# Homebrew_Companion_Board_v2.net
KiCad netlist of a schematic drawn in EAGLE
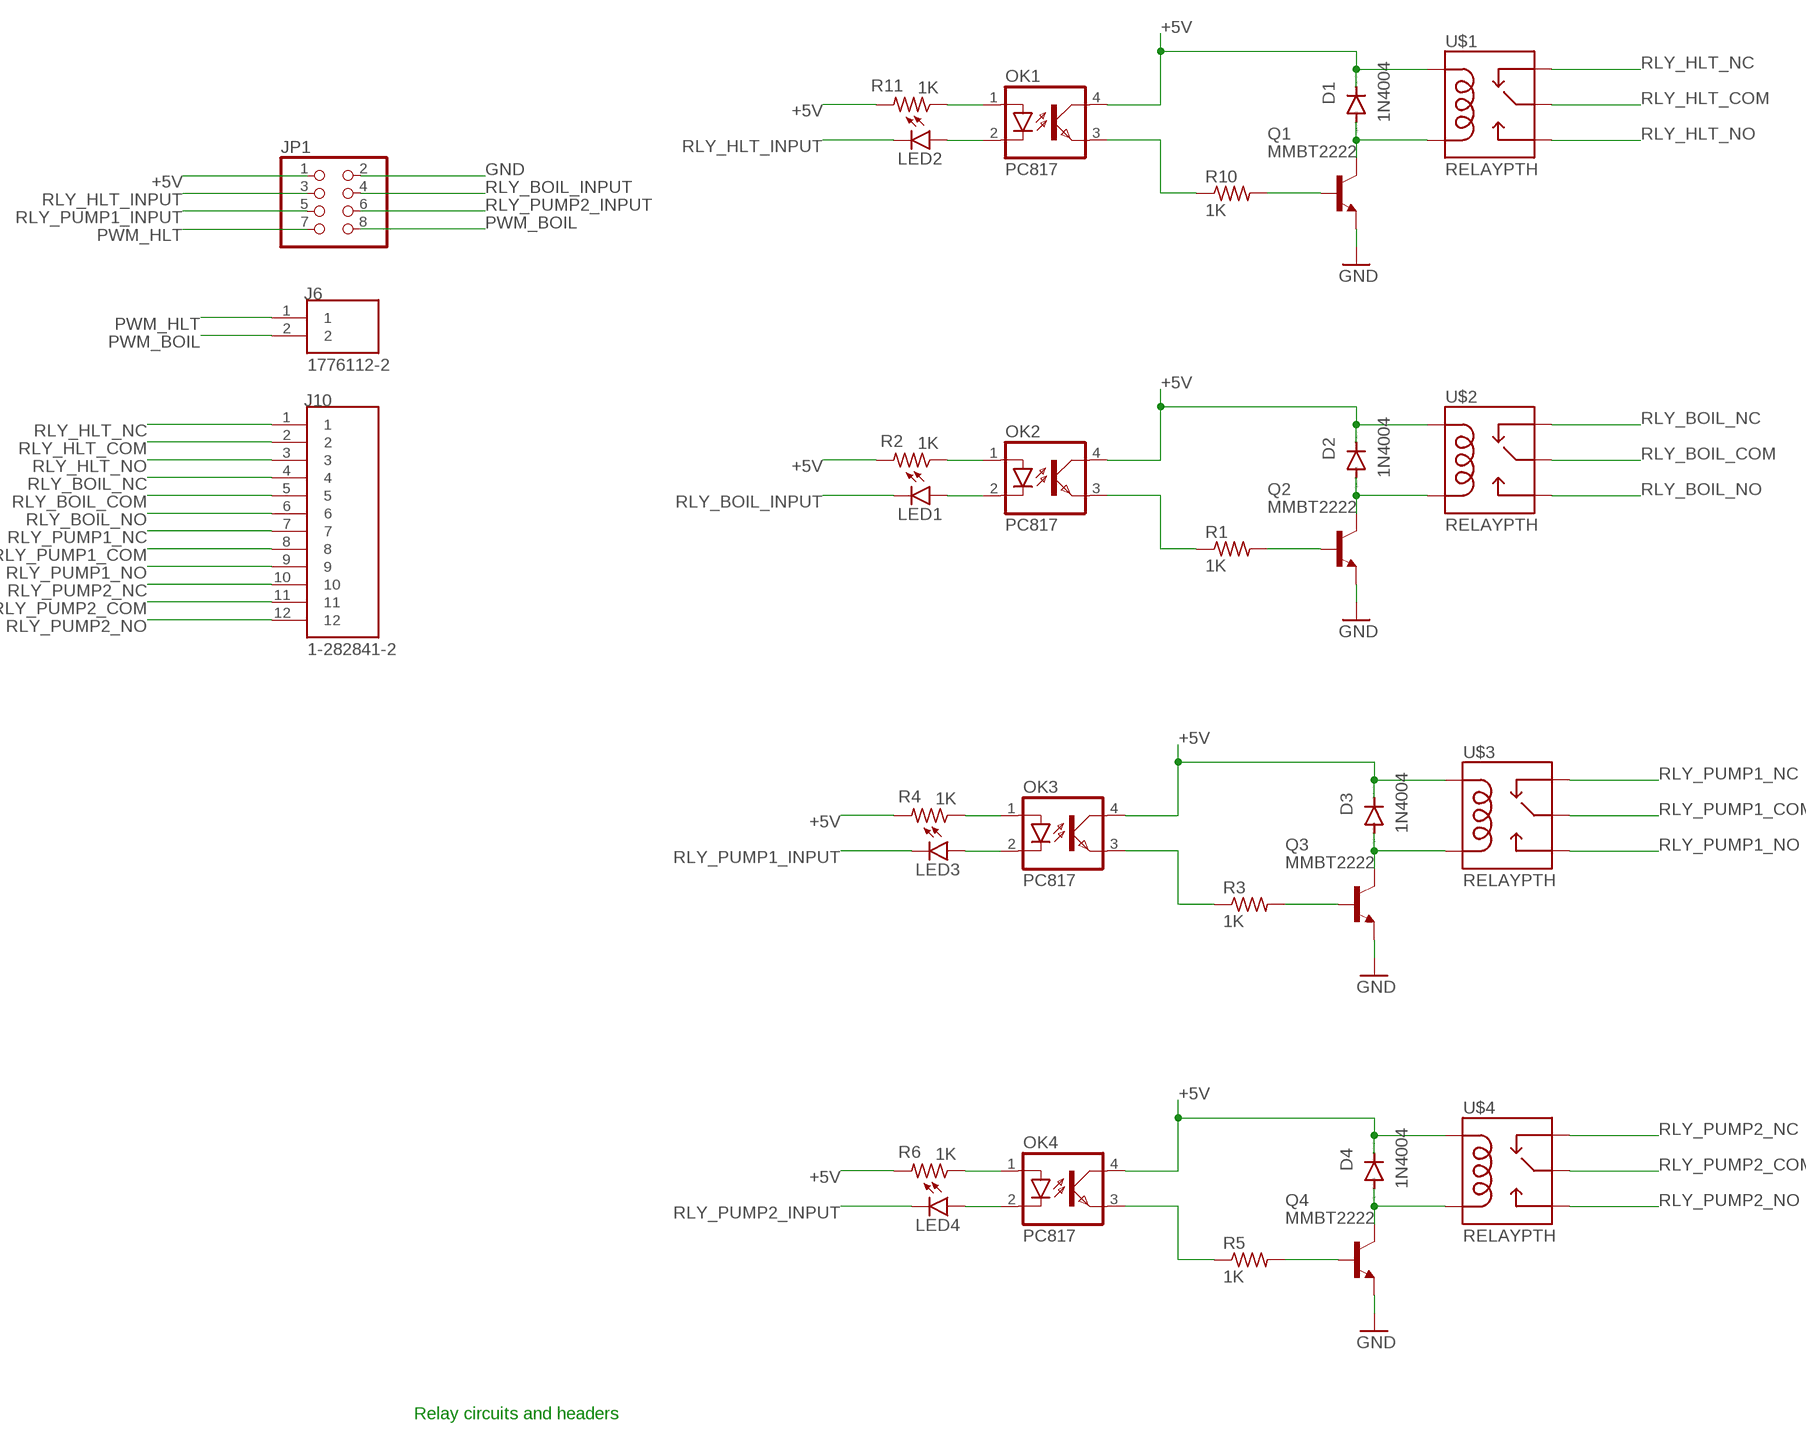
[diagram p0: schematic, sheet 1]

(export (version "E")
  (design (tool "Eeschema 10.0.6"))
  (components
    (comp (ref "D1")
      (value "1N4004")
      (footprint "eagle-import:DO41-10")
      (fields (field (name "MF") "DIODES INC.") (field (name "MPN") "1N4007-T"))
      (libsource (lib "eagle-import") (part "1N4004"))
    )
    (comp (ref "D2")
      (value "1N4004")
      (footprint "eagle-import:DO41-10")
      (fields (field (name "MF") "DIODES INC.") (field (name "MPN") "1N4007-T"))
      (libsource (lib "eagle-import") (part "1N4004"))
    )
    (comp (ref "D3")
      (value "1N4004")
      (footprint "eagle-import:DO41-10")
      (fields (field (name "MF") "DIODES INC.") (field (name "MPN") "1N4007-T"))
      (libsource (lib "eagle-import") (part "1N4004"))
    )
    (comp (ref "D4")
      (value "1N4004")
      (footprint "eagle-import:DO41-10")
      (fields (field (name "MF") "DIODES INC.") (field (name "MPN") "1N4007-T"))
      (libsource (lib "eagle-import") (part "1N4004"))
    )
    (comp (ref "J6")
      (value "1776112-2")
      (footprint "eagle-import:TE_1776112-2")
      (fields (field (name "MF") "TE Connectivity") (field (name "MF_1") "AMP - TE CONNECTIVITY"))
      (libsource (lib "eagle-import") (part "1776112-2"))
    )
    (comp (ref "J10")
      (value "1-282841-2")
      (footprint "eagle-import:TE_1-282841-2")
      (fields (field (name "MF") "TE Connectivity") (field (name "MF_1") "AMP - TE CONNECTIVITY"))
      (libsource (lib "eagle-import") (part "1-282841-2"))
    )
    (comp (ref "JP1")
      (value "PINHD-2X4")
      (footprint "eagle-import:2X04")
      (fields (field (name "MF") "AMP - TE CONNECTIVITY") (field (name "MPN") "826634-4"))
      (libsource (lib "eagle-import") (part "PINHD-2X4"))
    )
    (comp (ref "LED1")
      (value "LEDCHIP-LED0805")
      (footprint "eagle-import:CHIP-LED0805")
      (fields (field (name "MF") "DIALIGHT") (field (name "MPN") "5988110107F"))
      (libsource (lib "eagle-import") (part "LEDCHIP-LED0805"))
    )
    (comp (ref "LED2")
      (value "LEDCHIP-LED0805")
      (footprint "eagle-import:CHIP-LED0805")
      (fields (field (name "MF") "DIALIGHT") (field (name "MPN") "5988110107F"))
      (libsource (lib "eagle-import") (part "LEDCHIP-LED0805"))
    )
    (comp (ref "LED3")
      (value "LEDCHIP-LED0805")
      (footprint "eagle-import:CHIP-LED0805")
      (fields (field (name "MF") "DIALIGHT") (field (name "MPN") "5988110107F"))
      (libsource (lib "eagle-import") (part "LEDCHIP-LED0805"))
    )
    (comp (ref "LED4")
      (value "LEDCHIP-LED0805")
      (footprint "eagle-import:CHIP-LED0805")
      (fields (field (name "MF") "DIALIGHT") (field (name "MPN") "5988110107F"))
      (libsource (lib "eagle-import") (part "LEDCHIP-LED0805"))
    )
    (comp (ref "OK1")
      (value "PC817")
      (footprint "eagle-import:DIL04")
      (fields
        (field (name "MPN") "PC817X4J000F")
        (field (name "MF") "BROADCOM")
        (field (name "MPN_1") "HCPL-817-000E")
        (field (name "OC_NEWARK") "36J9610")
      )
      (libsource (lib "eagle-import") (part "PC817"))
    )
    (comp (ref "OK2")
      (value "PC817")
      (footprint "eagle-import:DIL04")
      (fields
        (field (name "MPN") "PC817X4J000F")
        (field (name "MF") "BROADCOM")
        (field (name "MPN_1") "HCPL-817-000E")
        (field (name "OC_NEWARK") "36J9610")
      )
      (libsource (lib "eagle-import") (part "PC817"))
    )
    (comp (ref "OK3")
      (value "PC817")
      (footprint "eagle-import:DIL04")
      (fields
        (field (name "MPN") "PC817X4J000F")
        (field (name "MF") "BROADCOM")
        (field (name "MPN_1") "HCPL-817-000E")
        (field (name "OC_NEWARK") "36J9610")
      )
      (libsource (lib "eagle-import") (part "PC817"))
    )
    (comp (ref "OK4")
      (value "PC817")
      (footprint "eagle-import:DIL04")
      (fields
        (field (name "MPN") "PC817X4J000F")
        (field (name "MF") "BROADCOM")
        (field (name "MPN_1") "HCPL-817-000E")
        (field (name "OC_NEWARK") "36J9610")
      )
      (libsource (lib "eagle-import") (part "PC817"))
    )
    (comp (ref "Q1")
      (value "MMBT2222")
      (footprint "eagle-import:SOT23-BEC")
      (fields
        (field (name "MF") "ON Semiconductor")
        (field (name "MF_1") "DIODES INC.")
        (field (name "MPN") "MMBT2222A-7-F")
      )
      (libsource (lib "eagle-import") (part "MMBT2222"))
    )
    (comp (ref "Q2")
      (value "MMBT2222")
      (footprint "eagle-import:SOT23-BEC")
      (fields
        (field (name "MF") "ON Semiconductor")
        (field (name "MF_1") "DIODES INC.")
        (field (name "MPN") "MMBT2222A-7-F")
      )
      (libsource (lib "eagle-import") (part "MMBT2222"))
    )
    (comp (ref "Q3")
      (value "MMBT2222")
      (footprint "eagle-import:SOT23-BEC")
      (fields
        (field (name "MF") "ON Semiconductor")
        (field (name "MF_1") "DIODES INC.")
        (field (name "MPN") "MMBT2222A-7-F")
      )
      (libsource (lib "eagle-import") (part "MMBT2222"))
    )
    (comp (ref "Q4")
      (value "MMBT2222")
      (footprint "eagle-import:SOT23-BEC")
      (fields
        (field (name "MF") "ON Semiconductor")
        (field (name "MF_1") "DIODES INC.")
        (field (name "MPN") "MMBT2222A-7-F")
      )
      (libsource (lib "eagle-import") (part "MMBT2222"))
    )
    (comp (ref "R1")
      (value "1K")
      (footprint "eagle-import:R0603")
      (fields (field (name "MF") "YAGEO") (field (name "MPN") "AC0402FR-071KL"))
      (libsource (lib "eagle-import") (part "R-US_R0603"))
    )
    (comp (ref "R2")
      (value "1K")
      (footprint "eagle-import:R0603")
      (fields (field (name "MF") "YAGEO") (field (name "MPN") "AC0402FR-071KL"))
      (libsource (lib "eagle-import") (part "R-US_R0603"))
    )
    (comp (ref "R3")
      (value "1K")
      (footprint "eagle-import:R0603")
      (fields (field (name "MF") "YAGEO") (field (name "MPN") "AC0402FR-071KL"))
      (libsource (lib "eagle-import") (part "R-US_R0603"))
    )
    (comp (ref "R4")
      (value "1K")
      (footprint "eagle-import:R0603")
      (fields (field (name "MF") "YAGEO") (field (name "MPN") "AC0402FR-071KL"))
      (libsource (lib "eagle-import") (part "R-US_R0603"))
    )
    (comp (ref "R5")
      (value "1K")
      (footprint "eagle-import:R0603")
      (fields (field (name "MF") "YAGEO") (field (name "MPN") "AC0402FR-071KL"))
      (libsource (lib "eagle-import") (part "R-US_R0603"))
    )
    (comp (ref "R6")
      (value "1K")
      (footprint "eagle-import:R0603")
      (fields (field (name "MF") "YAGEO") (field (name "MPN") "AC0402FR-071KL"))
      (libsource (lib "eagle-import") (part "R-US_R0603"))
    )
    (comp (ref "R10")
      (value "1K")
      (footprint "eagle-import:R0603")
      (fields (field (name "MF") "YAGEO") (field (name "MPN") "AC0402FR-071KL"))
      (libsource (lib "eagle-import") (part "R-US_R0603"))
    )
    (comp (ref "R11")
      (value "1K")
      (footprint "eagle-import:R0603")
      (fields (field (name "MF") "YAGEO") (field (name "MPN") "AC0402FR-071KL"))
      (libsource (lib "eagle-import") (part "R-US_R0603"))
    )
    (comp (ref "U$1")
      (value "RELAYPTH")
      (footprint "eagle-import:SRD-05VDC-SL-C")
      (libsource (lib "eagle-import") (part "RELAYPTH"))
    )
    (comp (ref "U$2")
      (value "RELAYPTH")
      (footprint "eagle-import:SRD-05VDC-SL-C")
      (libsource (lib "eagle-import") (part "RELAYPTH"))
    )
    (comp (ref "U$3")
      (value "RELAYPTH")
      (footprint "eagle-import:SRD-05VDC-SL-C")
      (libsource (lib "eagle-import") (part "RELAYPTH"))
    )
    (comp (ref "U$4")
      (value "RELAYPTH")
      (footprint "eagle-import:SRD-05VDC-SL-C")
      (libsource (lib "eagle-import") (part "RELAYPTH"))
    )
  )
  (nets
    (net (code "1") (name "/+5V") (class "Default")
      (node (ref "D1") (pin "C") (pinfunction "C_C") (pintype "passive"))
      (node (ref "D2") (pin "C") (pinfunction "C_C") (pintype "passive"))
      (node (ref "D3") (pin "C") (pinfunction "C_C") (pintype "passive"))
      (node (ref "D4") (pin "C") (pinfunction "C_C") (pintype "passive"))
      (node (ref "JP1") (pin "1") (pinfunction "1_1") (pintype "passive"))
      (node (ref "OK1") (pin "4") (pinfunction "COL_4") (pintype "passive"))
      (node (ref "OK2") (pin "4") (pinfunction "COL_4") (pintype "passive"))
      (node (ref "OK3") (pin "4") (pinfunction "COL_4") (pintype "passive"))
      (node (ref "OK4") (pin "4") (pinfunction "COL_4") (pintype "passive"))
      (node (ref "R11") (pin "2") (pinfunction "2_2") (pintype "passive"))
      (node (ref "R2") (pin "2") (pinfunction "2_2") (pintype "passive"))
      (node (ref "R4") (pin "2") (pinfunction "2_2") (pintype "passive"))
      (node (ref "R6") (pin "2") (pinfunction "2_2") (pintype "passive"))
      (node (ref "U$1") (pin "COIL1") (pinfunction "COIL1_COIL1") (pintype "bidirectional"))
      (node (ref "U$2") (pin "COIL1") (pinfunction "COIL1_COIL1") (pintype "bidirectional"))
      (node (ref "U$3") (pin "COIL1") (pinfunction "COIL1_COIL1") (pintype "bidirectional"))
      (node (ref "U$4") (pin "COIL1") (pinfunction "COIL1_COIL1") (pintype "bidirectional"))
    )
    (net (code "2") (name "/PWM_BOIL") (class "Default")
      (node (ref "J6") (pin "2") (pinfunction "2_2") (pintype "passive"))
      (node (ref "JP1") (pin "8") (pinfunction "8_8") (pintype "passive"))
    )
    (net (code "3") (name "/PWM_HLT") (class "Default")
      (node (ref "J6") (pin "1") (pinfunction "1_1") (pintype "passive"))
      (node (ref "JP1") (pin "7") (pinfunction "7_7") (pintype "passive"))
    )
    (net (code "4") (name "/RLY_BOIL_COM") (class "Default")
      (node (ref "J10") (pin "5") (pinfunction "5_5") (pintype "passive"))
      (node (ref "U$2") (pin "SWCOMMON") (pinfunction "SWCOMMON_SWCOMMON") (pintype "bidirectional"))
    )
    (net (code "5") (name "/RLY_BOIL_INPUT") (class "Default")
      (node (ref "JP1") (pin "4") (pinfunction "4_4") (pintype "passive"))
      (node (ref "LED1") (pin "C") (pinfunction "C_C") (pintype "passive"))
    )
    (net (code "6") (name "/RLY_BOIL_NC") (class "Default")
      (node (ref "J10") (pin "4") (pinfunction "4_4") (pintype "passive"))
      (node (ref "U$2") (pin "SWCLOSED") (pinfunction "SWCLOSE_SWCLOSED") (pintype "bidirectional"))
    )
    (net (code "7") (name "/RLY_BOIL_NO") (class "Default")
      (node (ref "J10") (pin "6") (pinfunction "6_6") (pintype "passive"))
      (node (ref "U$2") (pin "SWOPEN") (pinfunction "SWOPEN_SWOPEN") (pintype "bidirectional"))
    )
    (net (code "8") (name "/RLY_HLT_COM") (class "Default")
      (node (ref "J10") (pin "2") (pinfunction "2_2") (pintype "passive"))
      (node (ref "U$1") (pin "SWCOMMON") (pinfunction "SWCOMMON_SWCOMMON") (pintype "bidirectional"))
    )
    (net (code "9") (name "/RLY_HLT_INPUT") (class "Default")
      (node (ref "JP1") (pin "3") (pinfunction "3_3") (pintype "passive"))
      (node (ref "LED2") (pin "C") (pinfunction "C_C") (pintype "passive"))
    )
    (net (code "10") (name "/RLY_HLT_NC") (class "Default")
      (node (ref "J10") (pin "1") (pinfunction "1_1") (pintype "passive"))
      (node (ref "U$1") (pin "SWCLOSED") (pinfunction "SWCLOSE_SWCLOSED") (pintype "bidirectional"))
    )
    (net (code "11") (name "/RLY_HLT_NO") (class "Default")
      (node (ref "J10") (pin "3") (pinfunction "3_3") (pintype "passive"))
      (node (ref "U$1") (pin "SWOPEN") (pinfunction "SWOPEN_SWOPEN") (pintype "bidirectional"))
    )
    (net (code "12") (name "/RLY_PUMP1_COM") (class "Default")
      (node (ref "J10") (pin "8") (pinfunction "8_8") (pintype "passive"))
      (node (ref "U$3") (pin "SWCOMMON") (pinfunction "SWCOMMON_SWCOMMON") (pintype "bidirectional"))
    )
    (net (code "13") (name "/RLY_PUMP1_INPUT") (class "Default")
      (node (ref "JP1") (pin "5") (pinfunction "5_5") (pintype "passive"))
      (node (ref "LED3") (pin "C") (pinfunction "C_C") (pintype "passive"))
    )
    (net (code "14") (name "/RLY_PUMP1_NC") (class "Default")
      (node (ref "J10") (pin "7") (pinfunction "7_7") (pintype "passive"))
      (node (ref "U$3") (pin "SWCLOSED") (pinfunction "SWCLOSE_SWCLOSED") (pintype "bidirectional"))
    )
    (net (code "15") (name "/RLY_PUMP1_NO") (class "Default")
      (node (ref "J10") (pin "9") (pinfunction "9_9") (pintype "passive"))
      (node (ref "U$3") (pin "SWOPEN") (pinfunction "SWOPEN_SWOPEN") (pintype "bidirectional"))
    )
    (net (code "16") (name "/RLY_PUMP2_COM") (class "Default")
      (node (ref "J10") (pin "11") (pinfunction "11_11") (pintype "passive"))
      (node (ref "U$4") (pin "SWCOMMON") (pinfunction "SWCOMMON_SWCOMMON") (pintype "bidirectional"))
    )
    (net (code "17") (name "/RLY_PUMP2_INPUT") (class "Default")
      (node (ref "JP1") (pin "6") (pinfunction "6_6") (pintype "passive"))
      (node (ref "LED4") (pin "C") (pinfunction "C_C") (pintype "passive"))
    )
    (net (code "18") (name "/RLY_PUMP2_NC") (class "Default")
      (node (ref "J10") (pin "10") (pinfunction "10_10") (pintype "passive"))
      (node (ref "U$4") (pin "SWCLOSED") (pinfunction "SWCLOSE_SWCLOSED") (pintype "bidirectional"))
    )
    (net (code "19") (name "/RLY_PUMP2_NO") (class "Default")
      (node (ref "J10") (pin "12") (pinfunction "12_12") (pintype "passive"))
      (node (ref "U$4") (pin "SWOPEN") (pinfunction "SWOPEN_SWOPEN") (pintype "bidirectional"))
    )
    (net (code "20") (name "GND") (class "Default")
      (node (ref "JP1") (pin "2") (pinfunction "2_2") (pintype "passive"))
      (node (ref "Q1") (pin "E") (pinfunction "E_E") (pintype "passive"))
      (node (ref "Q2") (pin "E") (pinfunction "E_E") (pintype "passive"))
      (node (ref "Q3") (pin "E") (pinfunction "E_E") (pintype "passive"))
      (node (ref "Q4") (pin "E") (pinfunction "E_E") (pintype "passive"))
    )
    (net (code "21") (name "Net-(D1-PadA)") (class "Default")
      (node (ref "D1") (pin "A") (pinfunction "A_A") (pintype "passive"))
      (node (ref "Q1") (pin "C") (pinfunction "C_C") (pintype "passive"))
      (node (ref "U$1") (pin "COIL0") (pinfunction "COIL0_COIL0") (pintype "bidirectional"))
    )
    (net (code "22") (name "Net-(D2-PadA)") (class "Default")
      (node (ref "D2") (pin "A") (pinfunction "A_A") (pintype "passive"))
      (node (ref "Q2") (pin "C") (pinfunction "C_C") (pintype "passive"))
      (node (ref "U$2") (pin "COIL0") (pinfunction "COIL0_COIL0") (pintype "bidirectional"))
    )
    (net (code "23") (name "Net-(D3-PadA)") (class "Default")
      (node (ref "D3") (pin "A") (pinfunction "A_A") (pintype "passive"))
      (node (ref "Q3") (pin "C") (pinfunction "C_C") (pintype "passive"))
      (node (ref "U$3") (pin "COIL0") (pinfunction "COIL0_COIL0") (pintype "bidirectional"))
    )
    (net (code "24") (name "Net-(D4-PadA)") (class "Default")
      (node (ref "D4") (pin "A") (pinfunction "A_A") (pintype "passive"))
      (node (ref "Q4") (pin "C") (pinfunction "C_C") (pintype "passive"))
      (node (ref "U$4") (pin "COIL0") (pinfunction "COIL0_COIL0") (pintype "bidirectional"))
    )
    (net (code "25") (name "Net-(OK1-A)") (class "Default")
      (node (ref "OK1") (pin "1") (pinfunction "A_1") (pintype "passive"))
      (node (ref "R11") (pin "1") (pinfunction "1_1") (pintype "passive"))
    )
    (net (code "26") (name "Net-(OK1-C)") (class "Default")
      (node (ref "LED2") (pin "A") (pinfunction "A_A") (pintype "passive"))
      (node (ref "OK1") (pin "2") (pinfunction "C_2") (pintype "passive"))
    )
    (net (code "27") (name "Net-(OK1-EMIT)") (class "Default")
      (node (ref "OK1") (pin "3") (pinfunction "EMIT_3") (pintype "passive"))
      (node (ref "R10") (pin "1") (pinfunction "1_1") (pintype "passive"))
    )
    (net (code "28") (name "Net-(OK2-A)") (class "Default")
      (node (ref "OK2") (pin "1") (pinfunction "A_1") (pintype "passive"))
      (node (ref "R2") (pin "1") (pinfunction "1_1") (pintype "passive"))
    )
    (net (code "29") (name "Net-(OK2-C)") (class "Default")
      (node (ref "LED1") (pin "A") (pinfunction "A_A") (pintype "passive"))
      (node (ref "OK2") (pin "2") (pinfunction "C_2") (pintype "passive"))
    )
    (net (code "30") (name "Net-(OK2-EMIT)") (class "Default")
      (node (ref "OK2") (pin "3") (pinfunction "EMIT_3") (pintype "passive"))
      (node (ref "R1") (pin "1") (pinfunction "1_1") (pintype "passive"))
    )
    (net (code "31") (name "Net-(OK3-A)") (class "Default")
      (node (ref "OK3") (pin "1") (pinfunction "A_1") (pintype "passive"))
      (node (ref "R4") (pin "1") (pinfunction "1_1") (pintype "passive"))
    )
    (net (code "32") (name "Net-(OK3-C)") (class "Default")
      (node (ref "LED3") (pin "A") (pinfunction "A_A") (pintype "passive"))
      (node (ref "OK3") (pin "2") (pinfunction "C_2") (pintype "passive"))
    )
    (net (code "33") (name "Net-(OK3-EMIT)") (class "Default")
      (node (ref "OK3") (pin "3") (pinfunction "EMIT_3") (pintype "passive"))
      (node (ref "R3") (pin "1") (pinfunction "1_1") (pintype "passive"))
    )
    (net (code "34") (name "Net-(OK4-A)") (class "Default")
      (node (ref "OK4") (pin "1") (pinfunction "A_1") (pintype "passive"))
      (node (ref "R6") (pin "1") (pinfunction "1_1") (pintype "passive"))
    )
    (net (code "35") (name "Net-(OK4-C)") (class "Default")
      (node (ref "LED4") (pin "A") (pinfunction "A_A") (pintype "passive"))
      (node (ref "OK4") (pin "2") (pinfunction "C_2") (pintype "passive"))
    )
    (net (code "36") (name "Net-(OK4-EMIT)") (class "Default")
      (node (ref "OK4") (pin "3") (pinfunction "EMIT_3") (pintype "passive"))
      (node (ref "R5") (pin "1") (pinfunction "1_1") (pintype "passive"))
    )
    (net (code "37") (name "Net-(Q1-PadB)") (class "Default")
      (node (ref "Q1") (pin "B") (pinfunction "B_B") (pintype "passive"))
      (node (ref "R10") (pin "2") (pinfunction "2_2") (pintype "passive"))
    )
    (net (code "38") (name "Net-(Q2-PadB)") (class "Default")
      (node (ref "Q2") (pin "B") (pinfunction "B_B") (pintype "passive"))
      (node (ref "R1") (pin "2") (pinfunction "2_2") (pintype "passive"))
    )
    (net (code "39") (name "Net-(Q3-PadB)") (class "Default")
      (node (ref "Q3") (pin "B") (pinfunction "B_B") (pintype "passive"))
      (node (ref "R3") (pin "2") (pinfunction "2_2") (pintype "passive"))
    )
    (net (code "40") (name "Net-(Q4-PadB)") (class "Default")
      (node (ref "Q4") (pin "B") (pinfunction "B_B") (pintype "passive"))
      (node (ref "R5") (pin "2") (pinfunction "2_2") (pintype "passive"))
    )
  )
)
